# Bi-Direction_Logic_Level_Converter.net
KiCad netlist of a schematic drawn in EAGLE
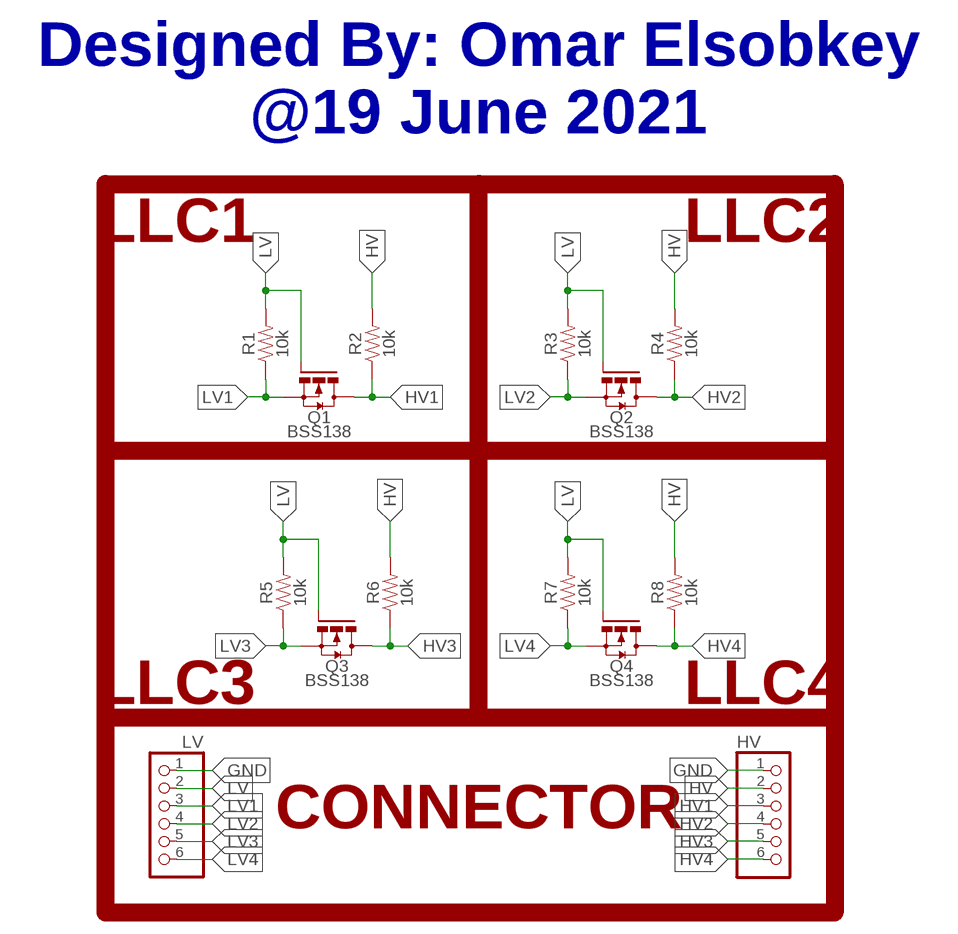
[diagram p0: schematic, sheet 1]

(export (version "E")
  (design (tool "Eeschema 10.0.6"))
  (components
    (comp (ref "HV")
      (value "PINHD-1X6")
      (footprint "eagle-import:1X06")
      (libsource (lib "eagle-import") (part "PINHD-1X6"))
    )
    (comp (ref "LV")
      (value "PINHD-1X6")
      (footprint "eagle-import:1X06")
      (libsource (lib "eagle-import") (part "PINHD-1X6"))
    )
    (comp (ref "Q1")
      (value "BSS138")
      (footprint "eagle-import:SOT23-3")
      (fields
        (field (name "DIGIKEY_PART_NUMBER") "BSS138CT-ND")
        (field (name "MANUFACTURER") "ON Semiconductor")
        (field (name "CREATED_BY") "PCBLayout.com")
      )
      (libsource (lib "eagle-import") (part "BSS138"))
    )
    (comp (ref "Q2")
      (value "BSS138")
      (footprint "eagle-import:SOT23-3")
      (fields
        (field (name "DIGIKEY_PART_NUMBER") "BSS138CT-ND")
        (field (name "MANUFACTURER") "ON Semiconductor")
        (field (name "CREATED_BY") "PCBLayout.com")
      )
      (libsource (lib "eagle-import") (part "BSS138"))
    )
    (comp (ref "Q3")
      (value "BSS138")
      (footprint "eagle-import:SOT23-3")
      (fields
        (field (name "DIGIKEY_PART_NUMBER") "BSS138CT-ND")
        (field (name "MANUFACTURER") "ON Semiconductor")
        (field (name "CREATED_BY") "PCBLayout.com")
      )
      (libsource (lib "eagle-import") (part "BSS138"))
    )
    (comp (ref "Q4")
      (value "BSS138")
      (footprint "eagle-import:SOT23-3")
      (fields
        (field (name "DIGIKEY_PART_NUMBER") "BSS138CT-ND")
        (field (name "MANUFACTURER") "ON Semiconductor")
        (field (name "CREATED_BY") "PCBLayout.com")
      )
      (libsource (lib "eagle-import") (part "BSS138"))
    )
    (comp (ref "R1")
      (value "10k")
      (footprint "eagle-import:1206")
      (libsource (lib "eagle-import") (part "RESISTOR1206"))
    )
    (comp (ref "R2")
      (value "10k")
      (footprint "eagle-import:1206")
      (libsource (lib "eagle-import") (part "RESISTOR1206"))
    )
    (comp (ref "R3")
      (value "10k")
      (footprint "eagle-import:1206")
      (libsource (lib "eagle-import") (part "RESISTOR1206"))
    )
    (comp (ref "R4")
      (value "10k")
      (footprint "eagle-import:1206")
      (libsource (lib "eagle-import") (part "RESISTOR1206"))
    )
    (comp (ref "R5")
      (value "10k")
      (footprint "eagle-import:1206")
      (libsource (lib "eagle-import") (part "RESISTOR1206"))
    )
    (comp (ref "R6")
      (value "10k")
      (footprint "eagle-import:1206")
      (libsource (lib "eagle-import") (part "RESISTOR1206"))
    )
    (comp (ref "R7")
      (value "10k")
      (footprint "eagle-import:1206")
      (libsource (lib "eagle-import") (part "RESISTOR1206"))
    )
    (comp (ref "R8")
      (value "10k")
      (footprint "eagle-import:1206")
      (libsource (lib "eagle-import") (part "RESISTOR1206"))
    )
  )
  (nets
    (net (code "1") (name "GND") (class "Default")
      (node (ref "HV") (pin "1") (pinfunction "1_1") (pintype "passive"))
      (node (ref "LV") (pin "1") (pinfunction "1_1") (pintype "passive"))
    )
    (net (code "2") (name "HV") (class "Default")
      (node (ref "HV") (pin "2") (pinfunction "2_2") (pintype "passive"))
      (node (ref "R2") (pin "2") (pinfunction "2_2") (pintype "passive"))
      (node (ref "R4") (pin "2") (pinfunction "2_2") (pintype "passive"))
      (node (ref "R6") (pin "2") (pinfunction "2_2") (pintype "passive"))
      (node (ref "R8") (pin "2") (pinfunction "2_2") (pintype "passive"))
    )
    (net (code "3") (name "HV1") (class "Default")
      (node (ref "HV") (pin "3") (pinfunction "3_3") (pintype "passive"))
      (node (ref "Q1") (pin "3") (pinfunction "D_3") (pintype "passive"))
      (node (ref "R2") (pin "1") (pinfunction "1_1") (pintype "passive"))
    )
    (net (code "4") (name "HV2") (class "Default")
      (node (ref "HV") (pin "4") (pinfunction "4_4") (pintype "passive"))
      (node (ref "Q2") (pin "3") (pinfunction "D_3") (pintype "passive"))
      (node (ref "R4") (pin "1") (pinfunction "1_1") (pintype "passive"))
    )
    (net (code "5") (name "HV3") (class "Default")
      (node (ref "HV") (pin "5") (pinfunction "5_5") (pintype "passive"))
      (node (ref "Q3") (pin "3") (pinfunction "D_3") (pintype "passive"))
      (node (ref "R6") (pin "1") (pinfunction "1_1") (pintype "passive"))
    )
    (net (code "6") (name "HV4") (class "Default")
      (node (ref "HV") (pin "6") (pinfunction "6_6") (pintype "passive"))
      (node (ref "Q4") (pin "3") (pinfunction "D_3") (pintype "passive"))
      (node (ref "R8") (pin "1") (pinfunction "1_1") (pintype "passive"))
    )
    (net (code "7") (name "LV") (class "Default")
      (node (ref "LV") (pin "2") (pinfunction "2_2") (pintype "passive"))
      (node (ref "Q1") (pin "1") (pinfunction "G_1") (pintype "passive"))
      (node (ref "Q2") (pin "1") (pinfunction "G_1") (pintype "passive"))
      (node (ref "Q3") (pin "1") (pinfunction "G_1") (pintype "passive"))
      (node (ref "Q4") (pin "1") (pinfunction "G_1") (pintype "passive"))
      (node (ref "R1") (pin "2") (pinfunction "2_2") (pintype "passive"))
      (node (ref "R3") (pin "2") (pinfunction "2_2") (pintype "passive"))
      (node (ref "R5") (pin "2") (pinfunction "2_2") (pintype "passive"))
      (node (ref "R7") (pin "2") (pinfunction "2_2") (pintype "passive"))
    )
    (net (code "8") (name "LV1") (class "Default")
      (node (ref "LV") (pin "3") (pinfunction "3_3") (pintype "passive"))
      (node (ref "Q1") (pin "2") (pinfunction "S_2") (pintype "passive"))
      (node (ref "R1") (pin "1") (pinfunction "1_1") (pintype "passive"))
    )
    (net (code "9") (name "LV2") (class "Default")
      (node (ref "LV") (pin "4") (pinfunction "4_4") (pintype "passive"))
      (node (ref "Q2") (pin "2") (pinfunction "S_2") (pintype "passive"))
      (node (ref "R3") (pin "1") (pinfunction "1_1") (pintype "passive"))
    )
    (net (code "10") (name "LV3") (class "Default")
      (node (ref "LV") (pin "5") (pinfunction "5_5") (pintype "passive"))
      (node (ref "Q3") (pin "2") (pinfunction "S_2") (pintype "passive"))
      (node (ref "R5") (pin "1") (pinfunction "1_1") (pintype "passive"))
    )
    (net (code "11") (name "LV4") (class "Default")
      (node (ref "LV") (pin "6") (pinfunction "6_6") (pintype "passive"))
      (node (ref "Q4") (pin "2") (pinfunction "S_2") (pintype "passive"))
      (node (ref "R7") (pin "1") (pinfunction "1_1") (pintype "passive"))
    )
  )
)
